# Esquematico.net
KiCad netlist of a schematic drawn in Altium Designer
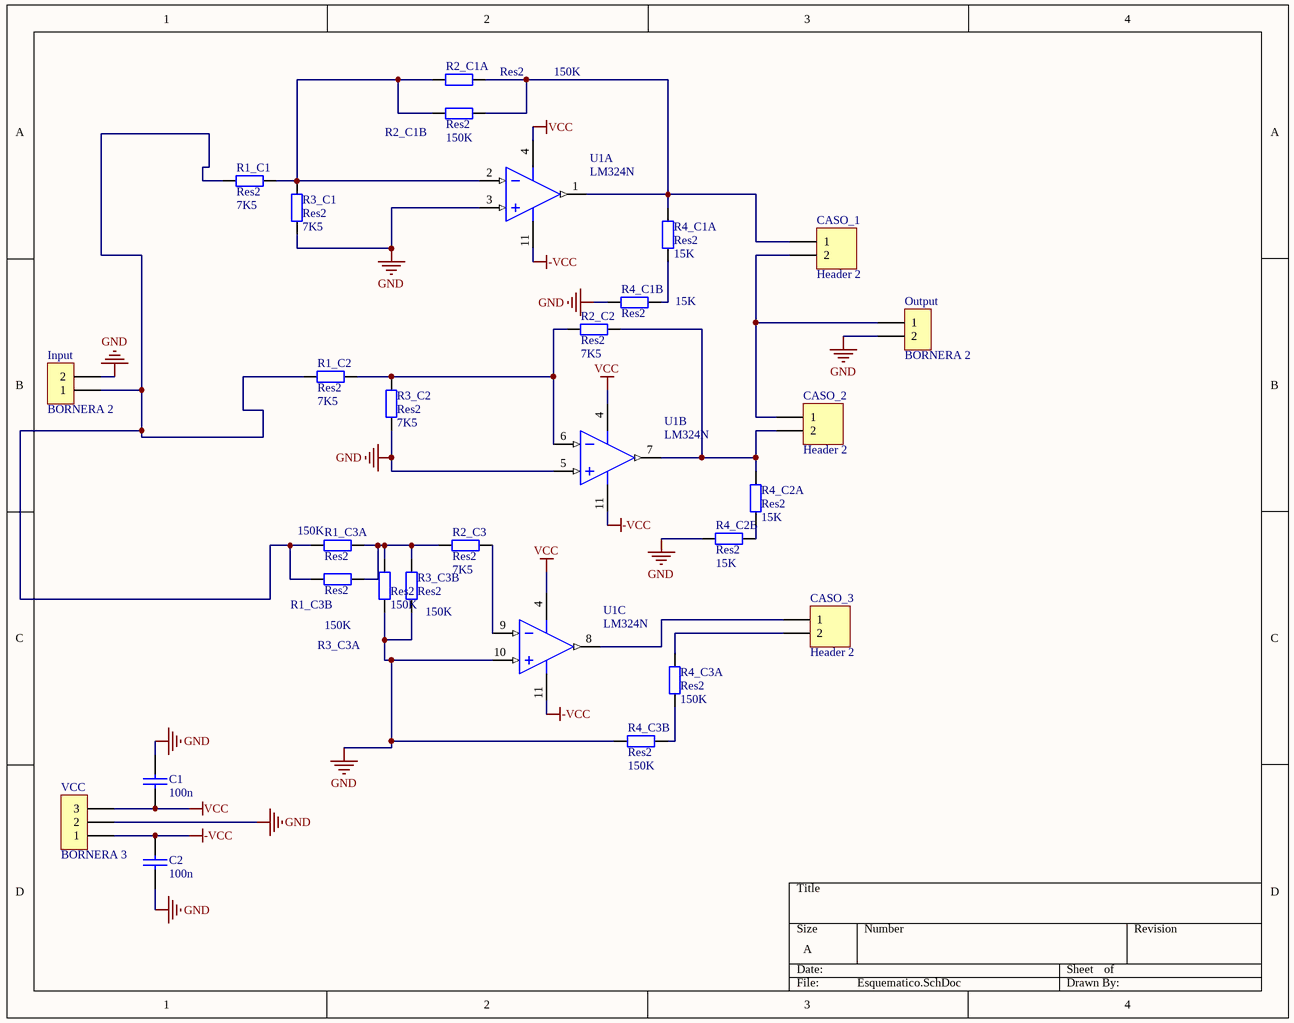
[diagram p0: Esquematico.SchDoc]

(export (version "E")
  (design (tool "Eeschema 10.0.6"))
  (components
    (comp (ref "C1") (value "100n") (footprint "CAP100") (libsource (lib "LIBEBAL") (part "CAP")))
    (comp (ref "C2") (value "100n") (footprint "CAP100") (libsource (lib "LIBEBAL") (part "CAP")))
    (comp (ref "CASO_1")
      (value "Header 2")
      (footprint "HDR1X2")
      (description "Header, 2-Pin")
      (fields (field (name "PUBLISHER") "Altium Limited"))
      (libsource (lib "Miscellaneous Connectors") (part "Header 2"))
    )
    (comp (ref "CASO_2")
      (value "Header 2")
      (footprint "HDR1X2")
      (description "Header, 2-Pin")
      (fields (field (name "PUBLISHER") "Altium Limited"))
      (libsource (lib "Miscellaneous Connectors") (part "Header 2"))
    )
    (comp (ref "CASO_3")
      (value "Header 2")
      (footprint "HDR1X2")
      (description "Header, 2-Pin")
      (fields (field (name "PUBLISHER") "Altium Limited"))
      (libsource (lib "Miscellaneous Connectors") (part "Header 2"))
    )
    (comp (ref "Input")
      (value "BORNERA 2")
      (footprint "BORNERA2")
      (libsource (lib "LIB PIO IX") (part "BORNERA 2"))
    )
    (comp (ref "Output") (value "BORNERA 2") (footprint "BORNERA2") (libsource (lib "") (part "BORNERA 2_1")))
    (comp (ref "R1_C1")
      (value "Res2")
      (footprint "AXIAL-0.4")
      (description "Resistor")
      (fields (field (name "ALTIUM_VALUE") "7K5") (field (name "PUBLISHER") "Altium Limited"))
      (libsource (lib "") (part "Res2_1"))
    )
    (comp (ref "R1_C2")
      (value "Res2")
      (footprint "AXIAL-0.4")
      (description "Resistor")
      (fields (field (name "ALTIUM_VALUE") "7K5") (field (name "PUBLISHER") "Altium Limited"))
      (libsource (lib "") (part "Res2_1"))
    )
    (comp (ref "R1_C3A")
      (value "Res2")
      (footprint "AXIAL-0.4")
      (description "Resistor")
      (fields (field (name "ALTIUM_VALUE") "150K") (field (name "PUBLISHER") "Altium Limited"))
      (libsource (lib "") (part "Res2_1"))
    )
    (comp (ref "R1_C3B")
      (value "Res2")
      (footprint "AXIAL-0.4")
      (description "Resistor")
      (fields (field (name "ALTIUM_VALUE") "150K") (field (name "PUBLISHER") "Altium Limited"))
      (libsource (lib "") (part "Res2_1"))
    )
    (comp (ref "R2_C1A")
      (value "Res2")
      (footprint "AXIAL-0.4")
      (description "Resistor")
      (fields (field (name "ALTIUM_VALUE") "150K") (field (name "PUBLISHER") "Altium Limited"))
      (libsource (lib "") (part "Res2_3"))
    )
    (comp (ref "R2_C1B")
      (value "Res2")
      (footprint "AXIAL-0.4")
      (description "Resistor")
      (fields (field (name "ALTIUM_VALUE") "150K") (field (name "PUBLISHER") "Altium Limited"))
      (libsource (lib "") (part "Res2_3"))
    )
    (comp (ref "R2_C2")
      (value "Res2")
      (footprint "AXIAL-0.4")
      (description "Resistor")
      (fields (field (name "ALTIUM_VALUE") "7K5") (field (name "PUBLISHER") "Altium Limited"))
      (libsource (lib "") (part "Res2_3"))
    )
    (comp (ref "R2_C3")
      (value "Res2")
      (footprint "AXIAL-0.4")
      (description "Resistor")
      (fields (field (name "ALTIUM_VALUE") "7K5") (field (name "PUBLISHER") "Altium Limited"))
      (libsource (lib "") (part "Res2_3"))
    )
    (comp (ref "R3_C1")
      (value "Res2")
      (footprint "AXIAL-0.4")
      (description "Resistor")
      (fields (field (name "ALTIUM_VALUE") "7K5") (field (name "PUBLISHER") "Altium Limited"))
      (libsource (lib "Miscellaneous Devices") (part "Res2"))
    )
    (comp (ref "R3_C2")
      (value "Res2")
      (footprint "AXIAL-0.4")
      (description "Resistor")
      (fields (field (name "ALTIUM_VALUE") "7K5") (field (name "PUBLISHER") "Altium Limited"))
      (libsource (lib "Miscellaneous Devices") (part "Res2"))
    )
    (comp (ref "R3_C3A")
      (value "Res2")
      (footprint "AXIAL-0.4")
      (description "Resistor")
      (fields (field (name "ALTIUM_VALUE") "150K") (field (name "PUBLISHER") "Altium Limited"))
      (libsource (lib "Miscellaneous Devices") (part "Res2"))
    )
    (comp (ref "R3_C3B")
      (value "Res2")
      (footprint "AXIAL-0.4")
      (description "Resistor")
      (fields (field (name "ALTIUM_VALUE") "150K") (field (name "PUBLISHER") "Altium Limited"))
      (libsource (lib "Miscellaneous Devices") (part "Res2"))
    )
    (comp (ref "R4_C1A")
      (value "Res2")
      (footprint "AXIAL-0.4")
      (description "Resistor")
      (fields (field (name "ALTIUM_VALUE") "15K") (field (name "PUBLISHER") "Altium Limited"))
      (libsource (lib "") (part "Res2_2"))
    )
    (comp (ref "R4_C1B")
      (value "Res2")
      (footprint "AXIAL-0.4")
      (description "Resistor")
      (fields (field (name "ALTIUM_VALUE") "15K") (field (name "PUBLISHER") "Altium Limited"))
      (libsource (lib "") (part "Res2_1"))
    )
    (comp (ref "R4_C2A")
      (value "Res2")
      (footprint "AXIAL-0.4")
      (description "Resistor")
      (fields (field (name "ALTIUM_VALUE") "15K") (field (name "PUBLISHER") "Altium Limited"))
      (libsource (lib "Miscellaneous Devices") (part "Res2"))
    )
    (comp (ref "R4_C2B")
      (value "Res2")
      (footprint "AXIAL-0.4")
      (description "Resistor")
      (fields (field (name "ALTIUM_VALUE") "15K") (field (name "PUBLISHER") "Altium Limited"))
      (libsource (lib "") (part "Res2_1"))
    )
    (comp (ref "R4_C3A")
      (value "Res2")
      (footprint "AXIAL-0.4")
      (description "Resistor")
      (fields (field (name "ALTIUM_VALUE") "150K") (field (name "PUBLISHER") "Altium Limited"))
      (libsource (lib "") (part "Res2_2"))
    )
    (comp (ref "R4_C3B")
      (value "Res2")
      (footprint "AXIAL-0.4")
      (description "Resistor")
      (fields (field (name "ALTIUM_VALUE") "150K") (field (name "PUBLISHER") "Altium Limited"))
      (libsource (lib "") (part "Res2_1"))
    )
    (comp (ref "U1")
      (value "LM324N")
      (footprint "N14A")
      (description "Low Power Quad Operational Amplifier, 14-pin MDIP")
      (fields
        (field (name "MANUFACTURER") "National Semiconductor")
        (field (name "PUBLISHER") "Altium Limited")
      )
      (libsource (lib "NSC Amplifier") (part "LM324N"))
    )
    (comp (ref "VCC")
      (value "BORNERA 3")
      (footprint "BORNERA3")
      (libsource (lib "LIB PIO IX") (part "BORNERA 3"))
    )
  )
  (nets
    (net (code "1") (name "-VCC") (class "Default")
      (node (ref "C2") (pin "1") (pinfunction "1_1") (pintype "passive"))
      (node (ref "U1") (pin "11") (pinfunction "GND_11") (pintype "power_in"))
      (node (ref "VCC") (pin "1") (pinfunction "1_1") (pintype "passive"))
    )
    (net (code "2") (name "GND") (class "Default")
      (node (ref "C1") (pin "1") (pinfunction "1_1") (pintype "passive"))
      (node (ref "C2") (pin "2") (pinfunction "2_2") (pintype "passive"))
      (node (ref "Input") (pin "2") (pinfunction "2_2") (pintype "passive"))
      (node (ref "Output") (pin "2") (pinfunction "2_2") (pintype "passive"))
      (node (ref "R3_C1") (pin "1") (pinfunction "1_1") (pintype "passive"))
      (node (ref "R3_C2") (pin "1") (pinfunction "1_1") (pintype "passive"))
      (node (ref "R3_C3A") (pin "1") (pinfunction "1_1") (pintype "passive"))
      (node (ref "R3_C3B") (pin "1") (pinfunction "1_1") (pintype "passive"))
      (node (ref "R4_C1B") (pin "1") (pinfunction "1_1") (pintype "passive"))
      (node (ref "R4_C2B") (pin "1") (pinfunction "1_1") (pintype "passive"))
      (node (ref "R4_C3B") (pin "1") (pinfunction "1_1") (pintype "passive"))
      (node (ref "U1") (pin "10") (pinfunction "IN3+_10") (pintype "input"))
      (node (ref "U1") (pin "3") (pinfunction "IN1+_3") (pintype "input"))
      (node (ref "U1") (pin "5") (pinfunction "IN2+_5") (pintype "input"))
      (node (ref "VCC") (pin "2") (pinfunction "2_2") (pintype "passive"))
    )
    (net (code "3") (name "Net-(CASO_1-Pad2)") (class "Default")
      (node (ref "CASO_1") (pin "2") (pinfunction "2_2") (pintype "passive"))
      (node (ref "CASO_2") (pin "1") (pinfunction "1_1") (pintype "passive"))
      (node (ref "Output") (pin "1") (pinfunction "1_1") (pintype "passive"))
    )
    (net (code "4") (name "Net-(CASO_3-Pad2)") (class "Default")
      (node (ref "CASO_3") (pin "2") (pinfunction "2_2") (pintype "passive"))
      (node (ref "R4_C3A") (pin "1") (pinfunction "1_1") (pintype "passive"))
    )
    (net (code "5") (name "Net-(Input-Pad1)") (class "Default")
      (node (ref "Input") (pin "1") (pinfunction "1_1") (pintype "passive"))
      (node (ref "R1_C1") (pin "1") (pinfunction "1_1") (pintype "passive"))
      (node (ref "R1_C2") (pin "1") (pinfunction "1_1") (pintype "passive"))
      (node (ref "R1_C3A") (pin "1") (pinfunction "1_1") (pintype "passive"))
      (node (ref "R1_C3B") (pin "1") (pinfunction "1_1") (pintype "passive"))
    )
    (net (code "6") (name "Net-(R1_C3A-Pad2)") (class "Default")
      (node (ref "R1_C3A") (pin "2") (pinfunction "2_2") (pintype "passive"))
      (node (ref "R1_C3B") (pin "2") (pinfunction "2_2") (pintype "passive"))
      (node (ref "R2_C3") (pin "2") (pinfunction "2_2") (pintype "passive"))
      (node (ref "R3_C3A") (pin "2") (pinfunction "2_2") (pintype "passive"))
      (node (ref "R3_C3B") (pin "2") (pinfunction "2_2") (pintype "passive"))
    )
    (net (code "7") (name "Net-(R4_C1A-Pad2)") (class "Default")
      (node (ref "R4_C1A") (pin "2") (pinfunction "2_2") (pintype "passive"))
      (node (ref "R4_C1B") (pin "2") (pinfunction "2_2") (pintype "passive"))
    )
    (net (code "8") (name "Net-(R4_C2A-Pad1)") (class "Default")
      (node (ref "R4_C2A") (pin "1") (pinfunction "1_1") (pintype "passive"))
      (node (ref "R4_C2B") (pin "2") (pinfunction "2_2") (pintype "passive"))
    )
    (net (code "9") (name "Net-(R4_C3A-Pad2)") (class "Default")
      (node (ref "R4_C3A") (pin "2") (pinfunction "2_2") (pintype "passive"))
      (node (ref "R4_C3B") (pin "2") (pinfunction "2_2") (pintype "passive"))
    )
    (net (code "10") (name "Net-(U1A-IN1-)") (class "Default")
      (node (ref "R1_C1") (pin "2") (pinfunction "2_2") (pintype "passive"))
      (node (ref "R2_C1A") (pin "2") (pinfunction "2_2") (pintype "passive"))
      (node (ref "R2_C1B") (pin "2") (pinfunction "2_2") (pintype "passive"))
      (node (ref "R3_C1") (pin "2") (pinfunction "2_2") (pintype "passive"))
      (node (ref "U1") (pin "2") (pinfunction "IN1-_2") (pintype "input"))
    )
    (net (code "11") (name "Net-(U1A-OUT1)") (class "Default")
      (node (ref "CASO_1") (pin "1") (pinfunction "1_1") (pintype "passive"))
      (node (ref "R2_C1A") (pin "1") (pinfunction "1_1") (pintype "passive"))
      (node (ref "R2_C1B") (pin "1") (pinfunction "1_1") (pintype "passive"))
      (node (ref "R4_C1A") (pin "1") (pinfunction "1_1") (pintype "passive"))
      (node (ref "U1") (pin "1") (pinfunction "OUT1_1") (pintype "output"))
    )
    (net (code "12") (name "Net-(U1B-IN2-)") (class "Default")
      (node (ref "R1_C2") (pin "2") (pinfunction "2_2") (pintype "passive"))
      (node (ref "R2_C2") (pin "2") (pinfunction "2_2") (pintype "passive"))
      (node (ref "R3_C2") (pin "2") (pinfunction "2_2") (pintype "passive"))
      (node (ref "U1") (pin "6") (pinfunction "IN2-_6") (pintype "input"))
    )
    (net (code "13") (name "Net-(U1B-OUT2)") (class "Default")
      (node (ref "CASO_2") (pin "2") (pinfunction "2_2") (pintype "passive"))
      (node (ref "R2_C2") (pin "1") (pinfunction "1_1") (pintype "passive"))
      (node (ref "R4_C2A") (pin "2") (pinfunction "2_2") (pintype "passive"))
      (node (ref "U1") (pin "7") (pinfunction "OUT2_7") (pintype "output"))
    )
    (net (code "14") (name "Net-(U1C-IN3-)") (class "Default")
      (node (ref "R2_C3") (pin "1") (pinfunction "1_1") (pintype "passive"))
      (node (ref "U1") (pin "9") (pinfunction "IN3-_9") (pintype "input"))
    )
    (net (code "15") (name "Net-(U1C-OUT3)") (class "Default")
      (node (ref "CASO_3") (pin "1") (pinfunction "1_1") (pintype "passive"))
      (node (ref "U1") (pin "8") (pinfunction "OUT3_8") (pintype "output"))
    )
    (net (code "16") (name "VCC") (class "Default")
      (node (ref "C1") (pin "2") (pinfunction "2_2") (pintype "passive"))
      (node (ref "U1") (pin "4") (pinfunction "V+_4") (pintype "power_in"))
      (node (ref "VCC") (pin "3") (pinfunction "3_3") (pintype "passive"))
    )
  )
)
